# Input.net
KiCad netlist of a schematic drawn in Altium Designer
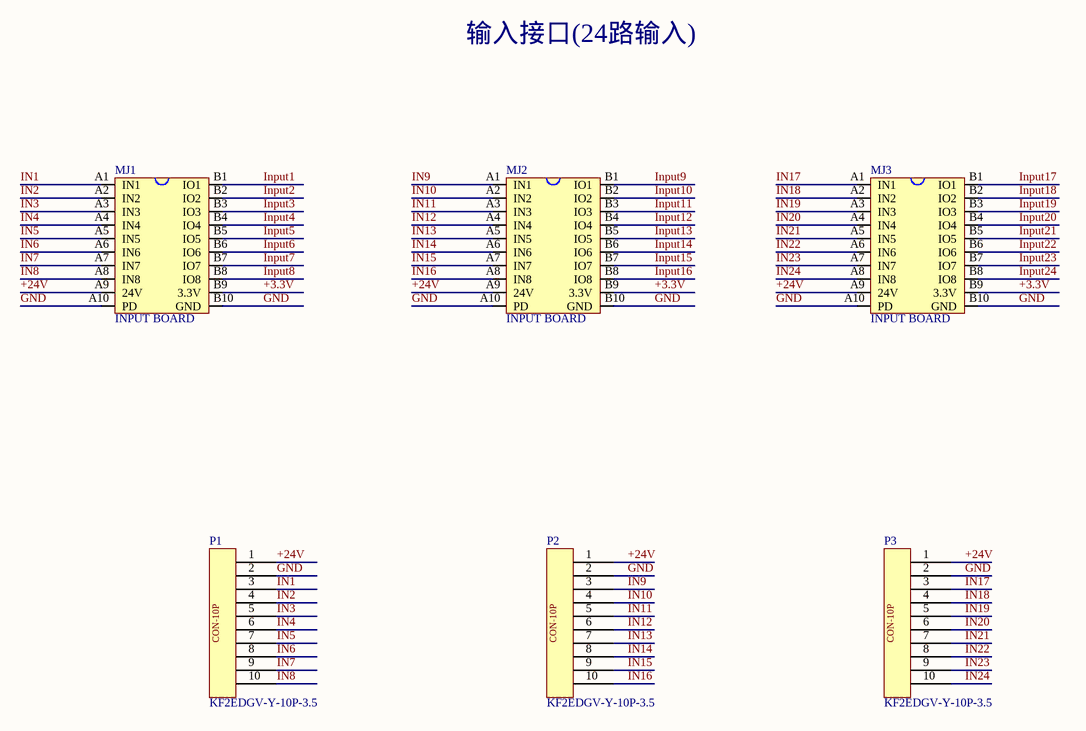
[diagram p0: Input.SchDoc]

(export (version "E")
  (design (tool "Eeschema 10.0.6"))
  (components
    (comp (ref "MJ1")
      (value "INPUT BOARD")
      (footprint "INPUT BOARD")
      (libsource (lib "Block Board Library SCH") (part "J-INPUT"))
    )
    (comp (ref "MJ2")
      (value "INPUT BOARD")
      (footprint "INPUT BOARD")
      (libsource (lib "Block Board Library SCH") (part "J-INPUT"))
    )
    (comp (ref "MJ3")
      (value "INPUT BOARD")
      (footprint "INPUT BOARD")
      (libsource (lib "Block Board Library SCH") (part "J-INPUT"))
    )
    (comp (ref "P1")
      (value "KF2EDGV-Y-10P-3.5")
      (footprint "KF2EDGV-Y-10P-3.5")
      (libsource (lib "Next_SCHlib") (part "CON-10P"))
    )
    (comp (ref "P2")
      (value "KF2EDGV-Y-10P-3.5")
      (footprint "KF2EDGV-Y-10P-3.5")
      (libsource (lib "Next_SCHlib") (part "CON-10P"))
    )
    (comp (ref "P3")
      (value "KF2EDGV-Y-10P-3.5")
      (footprint "KF2EDGV-Y-10P-3.5")
      (libsource (lib "Next_SCHlib") (part "CON-10P"))
    )
  )
  (nets
    (net (code "1") (name "/+3.3V") (class "Default")
      (node (ref "MJ1") (pin "B9") (pinfunction "3.3V_B9") (pintype "passive"))
      (node (ref "MJ2") (pin "B9") (pinfunction "3.3V_B9") (pintype "passive"))
      (node (ref "MJ3") (pin "B9") (pinfunction "3.3V_B9") (pintype "passive"))
    )
    (net (code "2") (name "/+24V") (class "Default")
      (node (ref "MJ1") (pin "A9") (pinfunction "24V_A9") (pintype "passive"))
      (node (ref "MJ2") (pin "A9") (pinfunction "24V_A9") (pintype "passive"))
      (node (ref "MJ3") (pin "A9") (pinfunction "24V_A9") (pintype "passive"))
      (node (ref "P1") (pin "1") (pinfunction "1_1") (pintype "passive"))
      (node (ref "P2") (pin "1") (pinfunction "1_1") (pintype "passive"))
      (node (ref "P3") (pin "1") (pinfunction "1_1") (pintype "passive"))
    )
    (net (code "3") (name "/GND") (class "Default")
      (node (ref "MJ1") (pin "A10") (pinfunction "PD_A10") (pintype "passive"))
      (node (ref "MJ1") (pin "B10") (pinfunction "GND_B10") (pintype "passive"))
      (node (ref "MJ2") (pin "A10") (pinfunction "PD_A10") (pintype "passive"))
      (node (ref "MJ2") (pin "B10") (pinfunction "GND_B10") (pintype "passive"))
      (node (ref "MJ3") (pin "A10") (pinfunction "PD_A10") (pintype "passive"))
      (node (ref "MJ3") (pin "B10") (pinfunction "GND_B10") (pintype "passive"))
      (node (ref "P1") (pin "2") (pinfunction "2_2") (pintype "passive"))
      (node (ref "P2") (pin "2") (pinfunction "2_2") (pintype "passive"))
      (node (ref "P3") (pin "2") (pinfunction "2_2") (pintype "passive"))
    )
    (net (code "4") (name "/IN1") (class "Default")
      (node (ref "MJ1") (pin "A1") (pinfunction "IN1_A1") (pintype "passive"))
      (node (ref "P1") (pin "3") (pinfunction "3_3") (pintype "passive"))
    )
    (net (code "5") (name "/IN2") (class "Default")
      (node (ref "MJ1") (pin "A2") (pinfunction "IN2_A2") (pintype "passive"))
      (node (ref "P1") (pin "4") (pinfunction "4_4") (pintype "passive"))
    )
    (net (code "6") (name "/IN3") (class "Default")
      (node (ref "MJ1") (pin "A3") (pinfunction "IN3_A3") (pintype "passive"))
      (node (ref "P1") (pin "5") (pinfunction "5_5") (pintype "passive"))
    )
    (net (code "7") (name "/IN4") (class "Default")
      (node (ref "MJ1") (pin "A4") (pinfunction "IN4_A4") (pintype "passive"))
      (node (ref "P1") (pin "6") (pinfunction "6_6") (pintype "passive"))
    )
    (net (code "8") (name "/IN5") (class "Default")
      (node (ref "MJ1") (pin "A5") (pinfunction "IN5_A5") (pintype "passive"))
      (node (ref "P1") (pin "7") (pinfunction "7_7") (pintype "passive"))
    )
    (net (code "9") (name "/IN6") (class "Default")
      (node (ref "MJ1") (pin "A6") (pinfunction "IN6_A6") (pintype "passive"))
      (node (ref "P1") (pin "8") (pinfunction "8_8") (pintype "passive"))
    )
    (net (code "10") (name "/IN7") (class "Default")
      (node (ref "MJ1") (pin "A7") (pinfunction "IN7_A7") (pintype "passive"))
      (node (ref "P1") (pin "9") (pinfunction "9_9") (pintype "passive"))
    )
    (net (code "11") (name "/IN8") (class "Default")
      (node (ref "MJ1") (pin "A8") (pinfunction "IN8_A8") (pintype "passive"))
      (node (ref "P1") (pin "10") (pinfunction "10_10") (pintype "passive"))
    )
    (net (code "12") (name "/IN9") (class "Default")
      (node (ref "MJ2") (pin "A1") (pinfunction "IN1_A1") (pintype "passive"))
      (node (ref "P2") (pin "3") (pinfunction "3_3") (pintype "passive"))
    )
    (net (code "13") (name "/IN10") (class "Default")
      (node (ref "MJ2") (pin "A2") (pinfunction "IN2_A2") (pintype "passive"))
      (node (ref "P2") (pin "4") (pinfunction "4_4") (pintype "passive"))
    )
    (net (code "14") (name "/IN11") (class "Default")
      (node (ref "MJ2") (pin "A3") (pinfunction "IN3_A3") (pintype "passive"))
      (node (ref "P2") (pin "5") (pinfunction "5_5") (pintype "passive"))
    )
    (net (code "15") (name "/IN12") (class "Default")
      (node (ref "MJ2") (pin "A4") (pinfunction "IN4_A4") (pintype "passive"))
      (node (ref "P2") (pin "6") (pinfunction "6_6") (pintype "passive"))
    )
    (net (code "16") (name "/IN13") (class "Default")
      (node (ref "MJ2") (pin "A5") (pinfunction "IN5_A5") (pintype "passive"))
      (node (ref "P2") (pin "7") (pinfunction "7_7") (pintype "passive"))
    )
    (net (code "17") (name "/IN14") (class "Default")
      (node (ref "MJ2") (pin "A6") (pinfunction "IN6_A6") (pintype "passive"))
      (node (ref "P2") (pin "8") (pinfunction "8_8") (pintype "passive"))
    )
    (net (code "18") (name "/IN15") (class "Default")
      (node (ref "MJ2") (pin "A7") (pinfunction "IN7_A7") (pintype "passive"))
      (node (ref "P2") (pin "9") (pinfunction "9_9") (pintype "passive"))
    )
    (net (code "19") (name "/IN16") (class "Default")
      (node (ref "MJ2") (pin "A8") (pinfunction "IN8_A8") (pintype "passive"))
      (node (ref "P2") (pin "10") (pinfunction "10_10") (pintype "passive"))
    )
    (net (code "20") (name "/IN17") (class "Default")
      (node (ref "MJ3") (pin "A1") (pinfunction "IN1_A1") (pintype "passive"))
      (node (ref "P3") (pin "3") (pinfunction "3_3") (pintype "passive"))
    )
    (net (code "21") (name "/IN18") (class "Default")
      (node (ref "MJ3") (pin "A2") (pinfunction "IN2_A2") (pintype "passive"))
      (node (ref "P3") (pin "4") (pinfunction "4_4") (pintype "passive"))
    )
    (net (code "22") (name "/IN19") (class "Default")
      (node (ref "MJ3") (pin "A3") (pinfunction "IN3_A3") (pintype "passive"))
      (node (ref "P3") (pin "5") (pinfunction "5_5") (pintype "passive"))
    )
    (net (code "23") (name "/IN20") (class "Default")
      (node (ref "MJ3") (pin "A4") (pinfunction "IN4_A4") (pintype "passive"))
      (node (ref "P3") (pin "6") (pinfunction "6_6") (pintype "passive"))
    )
    (net (code "24") (name "/IN21") (class "Default")
      (node (ref "MJ3") (pin "A5") (pinfunction "IN5_A5") (pintype "passive"))
      (node (ref "P3") (pin "7") (pinfunction "7_7") (pintype "passive"))
    )
    (net (code "25") (name "/IN22") (class "Default")
      (node (ref "MJ3") (pin "A6") (pinfunction "IN6_A6") (pintype "passive"))
      (node (ref "P3") (pin "8") (pinfunction "8_8") (pintype "passive"))
    )
    (net (code "26") (name "/IN23") (class "Default")
      (node (ref "MJ3") (pin "A7") (pinfunction "IN7_A7") (pintype "passive"))
      (node (ref "P3") (pin "9") (pinfunction "9_9") (pintype "passive"))
    )
    (net (code "27") (name "/IN24") (class "Default")
      (node (ref "MJ3") (pin "A8") (pinfunction "IN8_A8") (pintype "passive"))
      (node (ref "P3") (pin "10") (pinfunction "10_10") (pintype "passive"))
    )
    (net (code "28") (name "/Input1") (class "Default")
      (node (ref "MJ1") (pin "B1") (pinfunction "IO1_B1") (pintype "passive"))
    )
    (net (code "29") (name "/Input2") (class "Default")
      (node (ref "MJ1") (pin "B2") (pinfunction "IO2_B2") (pintype "passive"))
    )
    (net (code "30") (name "/Input3") (class "Default")
      (node (ref "MJ1") (pin "B3") (pinfunction "IO3_B3") (pintype "passive"))
    )
    (net (code "31") (name "/Input4") (class "Default")
      (node (ref "MJ1") (pin "B4") (pinfunction "IO4_B4") (pintype "passive"))
    )
    (net (code "32") (name "/Input5") (class "Default")
      (node (ref "MJ1") (pin "B5") (pinfunction "IO5_B5") (pintype "passive"))
    )
    (net (code "33") (name "/Input6") (class "Default")
      (node (ref "MJ1") (pin "B6") (pinfunction "IO6_B6") (pintype "passive"))
    )
    (net (code "34") (name "/Input7") (class "Default")
      (node (ref "MJ1") (pin "B7") (pinfunction "IO7_B7") (pintype "passive"))
    )
    (net (code "35") (name "/Input8") (class "Default")
      (node (ref "MJ1") (pin "B8") (pinfunction "IO8_B8") (pintype "passive"))
    )
    (net (code "36") (name "/Input9") (class "Default")
      (node (ref "MJ2") (pin "B1") (pinfunction "IO1_B1") (pintype "passive"))
    )
    (net (code "37") (name "/Input10") (class "Default")
      (node (ref "MJ2") (pin "B2") (pinfunction "IO2_B2") (pintype "passive"))
    )
    (net (code "38") (name "/Input11") (class "Default")
      (node (ref "MJ2") (pin "B3") (pinfunction "IO3_B3") (pintype "passive"))
    )
    (net (code "39") (name "/Input12") (class "Default")
      (node (ref "MJ2") (pin "B4") (pinfunction "IO4_B4") (pintype "passive"))
    )
    (net (code "40") (name "/Input13") (class "Default")
      (node (ref "MJ2") (pin "B5") (pinfunction "IO5_B5") (pintype "passive"))
    )
    (net (code "41") (name "/Input14") (class "Default")
      (node (ref "MJ2") (pin "B6") (pinfunction "IO6_B6") (pintype "passive"))
    )
    (net (code "42") (name "/Input15") (class "Default")
      (node (ref "MJ2") (pin "B7") (pinfunction "IO7_B7") (pintype "passive"))
    )
    (net (code "43") (name "/Input16") (class "Default")
      (node (ref "MJ2") (pin "B8") (pinfunction "IO8_B8") (pintype "passive"))
    )
    (net (code "44") (name "/Input17") (class "Default")
      (node (ref "MJ3") (pin "B1") (pinfunction "IO1_B1") (pintype "passive"))
    )
    (net (code "45") (name "/Input18") (class "Default")
      (node (ref "MJ3") (pin "B2") (pinfunction "IO2_B2") (pintype "passive"))
    )
    (net (code "46") (name "/Input19") (class "Default")
      (node (ref "MJ3") (pin "B3") (pinfunction "IO3_B3") (pintype "passive"))
    )
    (net (code "47") (name "/Input20") (class "Default")
      (node (ref "MJ3") (pin "B4") (pinfunction "IO4_B4") (pintype "passive"))
    )
    (net (code "48") (name "/Input21") (class "Default")
      (node (ref "MJ3") (pin "B5") (pinfunction "IO5_B5") (pintype "passive"))
    )
    (net (code "49") (name "/Input22") (class "Default")
      (node (ref "MJ3") (pin "B6") (pinfunction "IO6_B6") (pintype "passive"))
    )
    (net (code "50") (name "/Input23") (class "Default")
      (node (ref "MJ3") (pin "B7") (pinfunction "IO7_B7") (pintype "passive"))
    )
    (net (code "51") (name "/Input24") (class "Default")
      (node (ref "MJ3") (pin "B8") (pinfunction "IO8_B8") (pintype "passive"))
    )
  )
)
